# File_Nguyen_Ly.net
KiCad netlist of a schematic drawn in Altium Designer
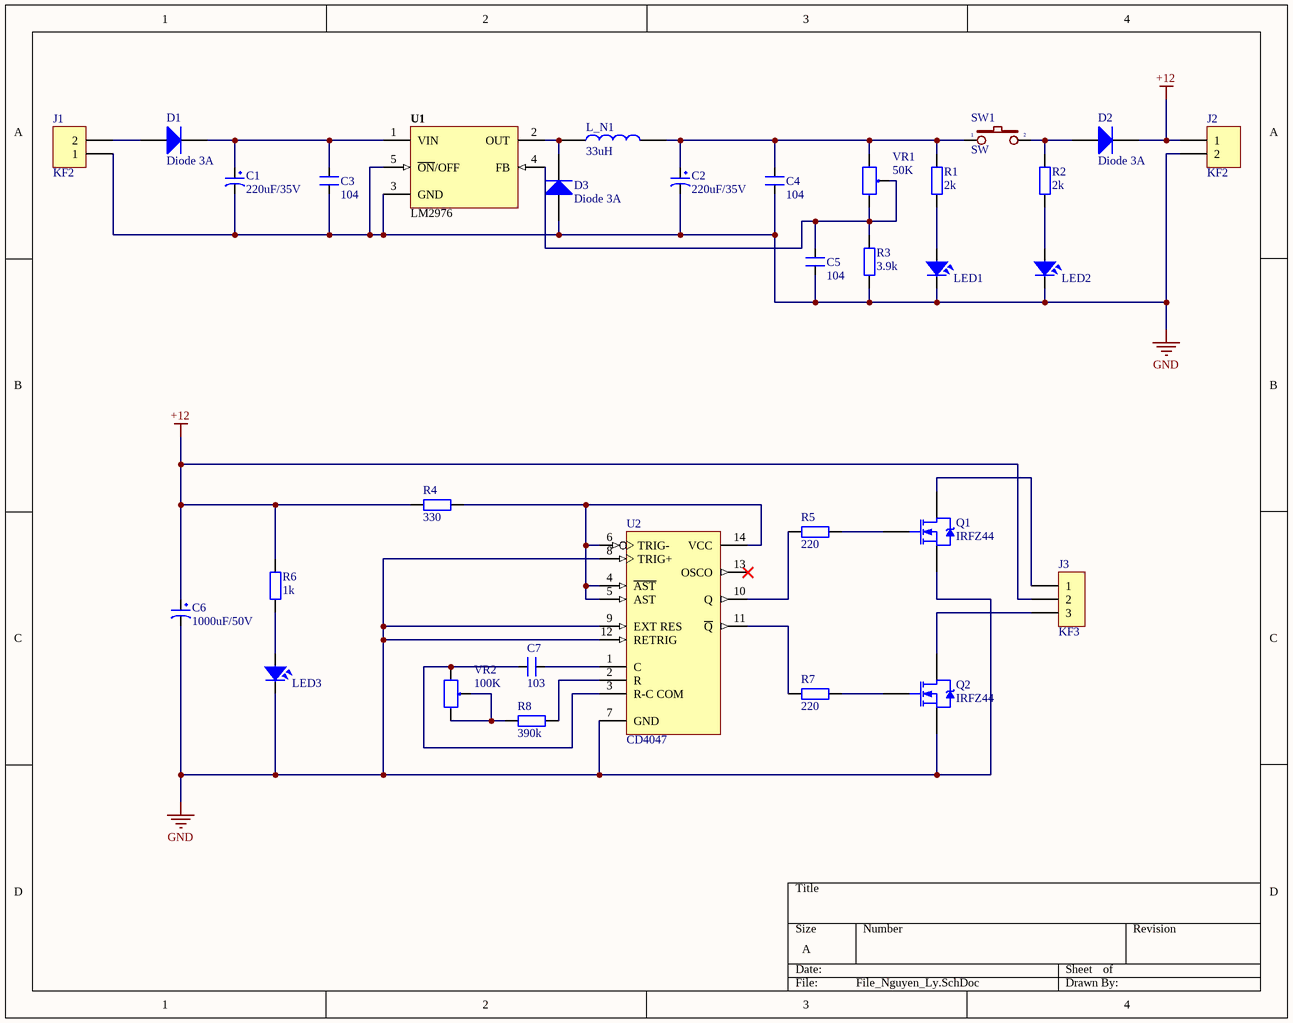
[diagram p0: File_Nguyen_Ly.SchDoc]

(export (version "E")
  (design (tool "Eeschema 10.0.6"))
  (components
    (comp (ref "C1")
      (value "220uF/35V")
      (footprint "CP1.5/3.4")
      (description "Cap 100uF/35V - 470uF/16V")
      (libsource (lib "Cty1") (part "CP3"))
    )
    (comp (ref "C2")
      (value "220uF/35V")
      (footprint "CP1.5/3.4")
      (description "Cap 100uF/35V - 470uF/16V")
      (libsource (lib "Cty1") (part "CP3"))
    )
    (comp (ref "C3")
      (value "104")
      (footprint "CN2")
      (description "Cap np 104 => 105pF")
      (libsource (lib "Cty1") (part "CN2"))
    )
    (comp (ref "C4")
      (value "104")
      (footprint "CN2")
      (description "Cap np 104 => 105pF")
      (libsource (lib "Cty1") (part "CN2"))
    )
    (comp (ref "C5")
      (value "104")
      (footprint "CN2")
      (description "Cap np 104 => 105pF")
      (libsource (lib "Cty1") (part "CN2"))
    )
    (comp (ref "C6")
      (value "1000uF/50V")
      (footprint "CP2/4")
      (description "Cap 2200uF/16V - 1000uF/50V")
      (libsource (lib "syhaunguyen") (part "CP5"))
    )
    (comp (ref "C7")
      (value "103")
      (footprint "CN1.5")
      (description "Cap np 682pF => 104pF")
      (libsource (lib "syhaunguyen") (part "CN1.5"))
    )
    (comp (ref "D1")
      (value "Diode 3A")
      (footprint "DIODE/POW/3A")
      (description "Diode Power")
      (fields (field (name "PUBLISHER") "Altium Limited"))
      (libsource (lib "Cty1") (part "Diode Power 3A"))
    )
    (comp (ref "D2")
      (value "Diode 3A")
      (footprint "DIODE/POW/3A")
      (description "Diode Power")
      (fields (field (name "PUBLISHER") "Altium Limited"))
      (libsource (lib "Cty1") (part "Diode Power 3A"))
    )
    (comp (ref "D3")
      (value "Diode 3A")
      (footprint "DIODE/POW/3A")
      (description "Diode Power")
      (fields (field (name "PUBLISHER") "Altium Limited"))
      (libsource (lib "Cty1") (part "Diode Power 3A"))
    )
    (comp (ref "J1")
      (value "KF2")
      (footprint "KF2-5.08")
      (fields
        (field (name "MANUFACTURER") "Würth Elektronik eiSos GmbH")
        (field (name "PARTNO") "691103110002")
        (field (name "CREATED BY") "Karrer Zheng")
      )
      (libsource (lib "") (part "KF2_1"))
    )
    (comp (ref "J2")
      (value "KF2")
      (footprint "KF2-7.62")
      (fields
        (field (name "MANUFACTURER") "Würth Elektronik eiSos GmbH")
        (field (name "PARTNO") "691103110002")
        (field (name "CREATED BY") "Karrer Zheng")
      )
      (libsource (lib "LIBRARY1") (part "KF2"))
    )
    (comp (ref "J3")
      (value "KF3")
      (footprint "KF3-7.62")
      (fields
        (field (name "MANUFACTURER") "Würth Elektronik eiSos GmbH")
        (field (name "PARTNO") "691103110003")
        (field (name "CREATED BY") "Karrer Zheng")
      )
      (libsource (lib "LIBRARY") (part "KF3"))
    )
    (comp (ref "LED1")
      (value "LED")
      (footprint "LED-5-Green")
      (description "LED Single colour Green and Red")
      (libsource (lib "syhaunguyen") (part "LED"))
    )
    (comp (ref "LED2")
      (value "LED")
      (footprint "LED-5-RED")
      (description "LED Single colour Green and Red")
      (libsource (lib "syhaunguyen") (part "LED"))
    )
    (comp (ref "LED3")
      (value "LED")
      (footprint "LED-5-BLUE")
      (description "LED Single colour Green and Red")
      (libsource (lib "syhaunguyen") (part "LED"))
    )
    (comp (ref "L_N1") (value "33uH") (footprint "100UH") (libsource (lib "Cty1") (part "INDUCTOR1")))
    (comp (ref "Q1") (value "IRFZ44") (footprint "TO220H2") (libsource (lib "LIBRARY") (part "IRFZ44")))
    (comp (ref "Q2") (value "IRFZ44") (footprint "TO220H2") (libsource (lib "LIBRARY") (part "IRFZ44")))
    (comp (ref "R1")
      (value "2k")
      (footprint "R1/4W")
      (description "Resistor 1/4W")
      (libsource (lib "syhaunguyen") (part "R1/4W"))
    )
    (comp (ref "R2")
      (value "2k")
      (footprint "R1/4W")
      (description "Resistor 1/4W")
      (libsource (lib "syhaunguyen") (part "R1/4W"))
    )
    (comp (ref "R3")
      (value "3.9k")
      (footprint "R1/4W")
      (description "Resistor 1/4W")
      (libsource (lib "syhaunguyen") (part "R1/4W"))
    )
    (comp (ref "R4")
      (value "330")
      (footprint "R1/4W")
      (description "Resistor 1/4W")
      (libsource (lib "syhaunguyen") (part "R1/4W"))
    )
    (comp (ref "R5")
      (value "220")
      (footprint "R1/2W")
      (description "Resistor 1/4W")
      (libsource (lib "syhaunguyen") (part "R1/4W"))
    )
    (comp (ref "R6")
      (value "1k")
      (footprint "R1/4W")
      (description "Resistor 1/4W")
      (libsource (lib "syhaunguyen") (part "R1/4W"))
    )
    (comp (ref "R7")
      (value "220")
      (footprint "R1/2W")
      (description "Resistor 1/4W")
      (libsource (lib "syhaunguyen") (part "R1/4W"))
    )
    (comp (ref "R8")
      (value "390k")
      (footprint "R1/4W")
      (description "Resistor 1/4W")
      (libsource (lib "syhaunguyen") (part "R1/4W"))
    )
    (comp (ref "SW1")
      (value "SW")
      (footprint "SW-DIP1-1")
      (description "Switch button 2 pin")
      (libsource (lib "LIBRARY") (part "SW2"))
    )
    (comp (ref "U1") (value "LM2976") (footprint "DIP5") (libsource (lib "LIBRARY") (part "LM2596")))
    (comp (ref "U2")
      (value "CD4047")
      (footprint "DIP14/W0.3")
      (libsource (lib "syhaunguyen") (part "CD4047"))
    )
    (comp (ref "VR1")
      (value "50K")
      (footprint "VR")
      (description "Var Resistor")
      (libsource (lib "syhaunguyen") (part "VR"))
    )
    (comp (ref "VR2")
      (value "100K")
      (footprint "VR")
      (description "Var Resistor")
      (libsource (lib "syhaunguyen") (part "VR"))
    )
  )
  (nets
    (net (code "1") (name "+12") (class "Default")
      (node (ref "C6") (pin "1") (pinfunction "1_1") (pintype "passive"))
      (node (ref "D2") (pin "2") (pinfunction "K_2") (pintype "passive"))
      (node (ref "J2") (pin "1") (pinfunction "1_1") (pintype "passive"))
      (node (ref "J3") (pin "2") (pinfunction "2_2") (pintype "passive"))
      (node (ref "R4") (pin "2") (pinfunction "2_2") (pintype "passive"))
      (node (ref "R6") (pin "2") (pinfunction "2_2") (pintype "passive"))
    )
    (net (code "2") (name "GND") (class "Default")
      (node (ref "C1") (pin "2") (pinfunction "2_2") (pintype "passive"))
      (node (ref "C2") (pin "2") (pinfunction "2_2") (pintype "passive"))
      (node (ref "C3") (pin "1") (pinfunction "1_1") (pintype "passive"))
      (node (ref "C4") (pin "1") (pinfunction "1_1") (pintype "passive"))
      (node (ref "C5") (pin "1") (pinfunction "1_1") (pintype "passive"))
      (node (ref "C6") (pin "2") (pinfunction "2_2") (pintype "passive"))
      (node (ref "D3") (pin "1") (pinfunction "A_1") (pintype "passive"))
      (node (ref "J1") (pin "1") (pinfunction "1_1") (pintype "passive"))
      (node (ref "J2") (pin "2") (pinfunction "2_2") (pintype "passive"))
      (node (ref "LED1") (pin "2") (pinfunction "2_2") (pintype "passive"))
      (node (ref "LED2") (pin "2") (pinfunction "2_2") (pintype "passive"))
      (node (ref "LED3") (pin "2") (pinfunction "2_2") (pintype "passive"))
      (node (ref "Q1") (pin "3") (pinfunction "S_3") (pintype "passive"))
      (node (ref "Q2") (pin "3") (pinfunction "S_3") (pintype "passive"))
      (node (ref "R3") (pin "1") (pinfunction "1_1") (pintype "passive"))
      (node (ref "U1") (pin "3") (pinfunction "GND_3") (pintype "power_in"))
      (node (ref "U1") (pin "5") (pinfunction "~{ON}/OFF_5") (pintype "input"))
      (node (ref "U2") (pin "12") (pinfunction "RETRIG_12") (pintype "input"))
      (node (ref "U2") (pin "7") (pinfunction "GND_7") (pintype "power_in"))
      (node (ref "U2") (pin "8") (pinfunction "TRIG+_8") (pintype "input"))
      (node (ref "U2") (pin "9") (pinfunction "EXT_RES_9") (pintype "input"))
    )
    (net (code "3") (name "Net-(C2-Pad1)") (class "Default")
      (node (ref "C2") (pin "1") (pinfunction "1_1") (pintype "passive"))
      (node (ref "C4") (pin "2") (pinfunction "2_2") (pintype "passive"))
      (node (ref "L_N1") (pin "2") (pinfunction "2_2") (pintype "passive"))
      (node (ref "R1") (pin "2") (pinfunction "2_2") (pintype "passive"))
      (node (ref "SW1") (pin "1") (pinfunction "1_1") (pintype "passive"))
      (node (ref "VR1") (pin "1") (pinfunction "1_1") (pintype "passive"))
    )
    (net (code "4") (name "Net-(D1-A)") (class "Default")
      (node (ref "D1") (pin "1") (pinfunction "A_1") (pintype "passive"))
      (node (ref "J1") (pin "2") (pinfunction "2_2") (pintype "passive"))
    )
    (net (code "5") (name "Net-(D1-K)") (class "Default")
      (node (ref "C1") (pin "1") (pinfunction "1_1") (pintype "passive"))
      (node (ref "C3") (pin "2") (pinfunction "2_2") (pintype "passive"))
      (node (ref "D1") (pin "2") (pinfunction "K_2") (pintype "passive"))
      (node (ref "U1") (pin "1") (pinfunction "VIN_1") (pintype "power_in"))
    )
    (net (code "6") (name "Net-(D2-A)") (class "Default")
      (node (ref "D2") (pin "1") (pinfunction "A_1") (pintype "passive"))
      (node (ref "R2") (pin "2") (pinfunction "2_2") (pintype "passive"))
      (node (ref "SW1") (pin "2") (pinfunction "2_2") (pintype "passive"))
    )
    (net (code "7") (name "Net-(D3-K)") (class "Default")
      (node (ref "D3") (pin "2") (pinfunction "K_2") (pintype "passive"))
      (node (ref "L_N1") (pin "1") (pinfunction "1_1") (pintype "passive"))
      (node (ref "U1") (pin "2") (pinfunction "OUT_2") (pintype "power_in"))
    )
    (net (code "8") (name "Net-(LED1-Pad1)") (class "Default")
      (node (ref "LED1") (pin "1") (pinfunction "1_1") (pintype "passive"))
      (node (ref "R1") (pin "1") (pinfunction "1_1") (pintype "passive"))
    )
    (net (code "9") (name "Net-(LED2-Pad1)") (class "Default")
      (node (ref "LED2") (pin "1") (pinfunction "1_1") (pintype "passive"))
      (node (ref "R2") (pin "1") (pinfunction "1_1") (pintype "passive"))
    )
    (net (code "10") (name "Net-(LED3-Pad1)") (class "Default")
      (node (ref "LED3") (pin "1") (pinfunction "1_1") (pintype "passive"))
      (node (ref "R6") (pin "1") (pinfunction "1_1") (pintype "passive"))
    )
    (net (code "11") (name "Net-(Q1-D)") (class "Default")
      (node (ref "J3") (pin "1") (pinfunction "1_1") (pintype "passive"))
      (node (ref "Q1") (pin "2") (pinfunction "D_2") (pintype "passive"))
    )
    (net (code "12") (name "Net-(Q1-G)") (class "Default")
      (node (ref "Q1") (pin "1") (pinfunction "G_1") (pintype "passive"))
      (node (ref "R5") (pin "1") (pinfunction "1_1") (pintype "passive"))
    )
    (net (code "13") (name "Net-(Q2-D)") (class "Default")
      (node (ref "J3") (pin "3") (pinfunction "3_3") (pintype "passive"))
      (node (ref "Q2") (pin "2") (pinfunction "D_2") (pintype "passive"))
    )
    (net (code "14") (name "Net-(Q2-G)") (class "Default")
      (node (ref "Q2") (pin "1") (pinfunction "G_1") (pintype "passive"))
      (node (ref "R7") (pin "1") (pinfunction "1_1") (pintype "passive"))
    )
    (net (code "15") (name "Net-(R8-Pad2)") (class "Default")
      (node (ref "R8") (pin "2") (pinfunction "2_2") (pintype "passive"))
      (node (ref "VR2") (pin "2") (pinfunction "2_2") (pintype "passive"))
      (node (ref "VR2") (pin "3") (pinfunction "3_3") (pintype "passive"))
    )
    (net (code "16") (name "Net-(U1-FB)") (class "Default")
      (node (ref "C5") (pin "2") (pinfunction "2_2") (pintype "passive"))
      (node (ref "R3") (pin "2") (pinfunction "2_2") (pintype "passive"))
      (node (ref "U1") (pin "4") (pinfunction "FB_4") (pintype "input"))
      (node (ref "VR1") (pin "2") (pinfunction "2_2") (pintype "passive"))
      (node (ref "VR1") (pin "3") (pinfunction "3_3") (pintype "passive"))
    )
    (net (code "17") (name "Net-(U2-AST)") (class "Default")
      (node (ref "R4") (pin "1") (pinfunction "1_1") (pintype "passive"))
      (node (ref "U2") (pin "14") (pinfunction "VCC_14") (pintype "power_in"))
      (node (ref "U2") (pin "4") (pinfunction "~{AST}_4") (pintype "input"))
      (node (ref "U2") (pin "5") (pinfunction "AST_5") (pintype "input"))
      (node (ref "U2") (pin "6") (pinfunction "TRIG-_6") (pintype "input"))
    )
    (net (code "18") (name "Net-(U2-C)") (class "Default")
      (node (ref "C7") (pin "2") (pinfunction "2_2") (pintype "passive"))
      (node (ref "U2") (pin "1") (pinfunction "C_1") (pintype "passive"))
    )
    (net (code "19") (name "Net-(U2-Q)") (class "Default")
      (node (ref "R5") (pin "2") (pinfunction "2_2") (pintype "passive"))
      (node (ref "U2") (pin "10") (pinfunction "Q_10") (pintype "output"))
    )
    (net (code "20") (name "Net-(U2-R)") (class "Default")
      (node (ref "R8") (pin "1") (pinfunction "1_1") (pintype "passive"))
      (node (ref "U2") (pin "2") (pinfunction "R_2") (pintype "passive"))
    )
    (net (code "21") (name "Net-(U2-R-C_COM)") (class "Default")
      (node (ref "C7") (pin "1") (pinfunction "1_1") (pintype "passive"))
      (node (ref "U2") (pin "3") (pinfunction "R-C_COM_3") (pintype "passive"))
      (node (ref "VR2") (pin "1") (pinfunction "1_1") (pintype "passive"))
    )
    (net (code "22") (name "Net-(U2-~{Q})") (class "Default")
      (node (ref "R7") (pin "2") (pinfunction "2_2") (pintype "passive"))
      (node (ref "U2") (pin "11") (pinfunction "~{Q}_11") (pintype "output"))
    )
    (net (code "23") (name "unconnected-(U2-OSCO-Pad13)") (class "Default")
      (node (ref "U2") (pin "13") (pinfunction "OSCO_13") (pintype "output+no_connect"))
    )
  )
)
